# MotorDrive.net
KiCad netlist of a schematic drawn in Altium Designer
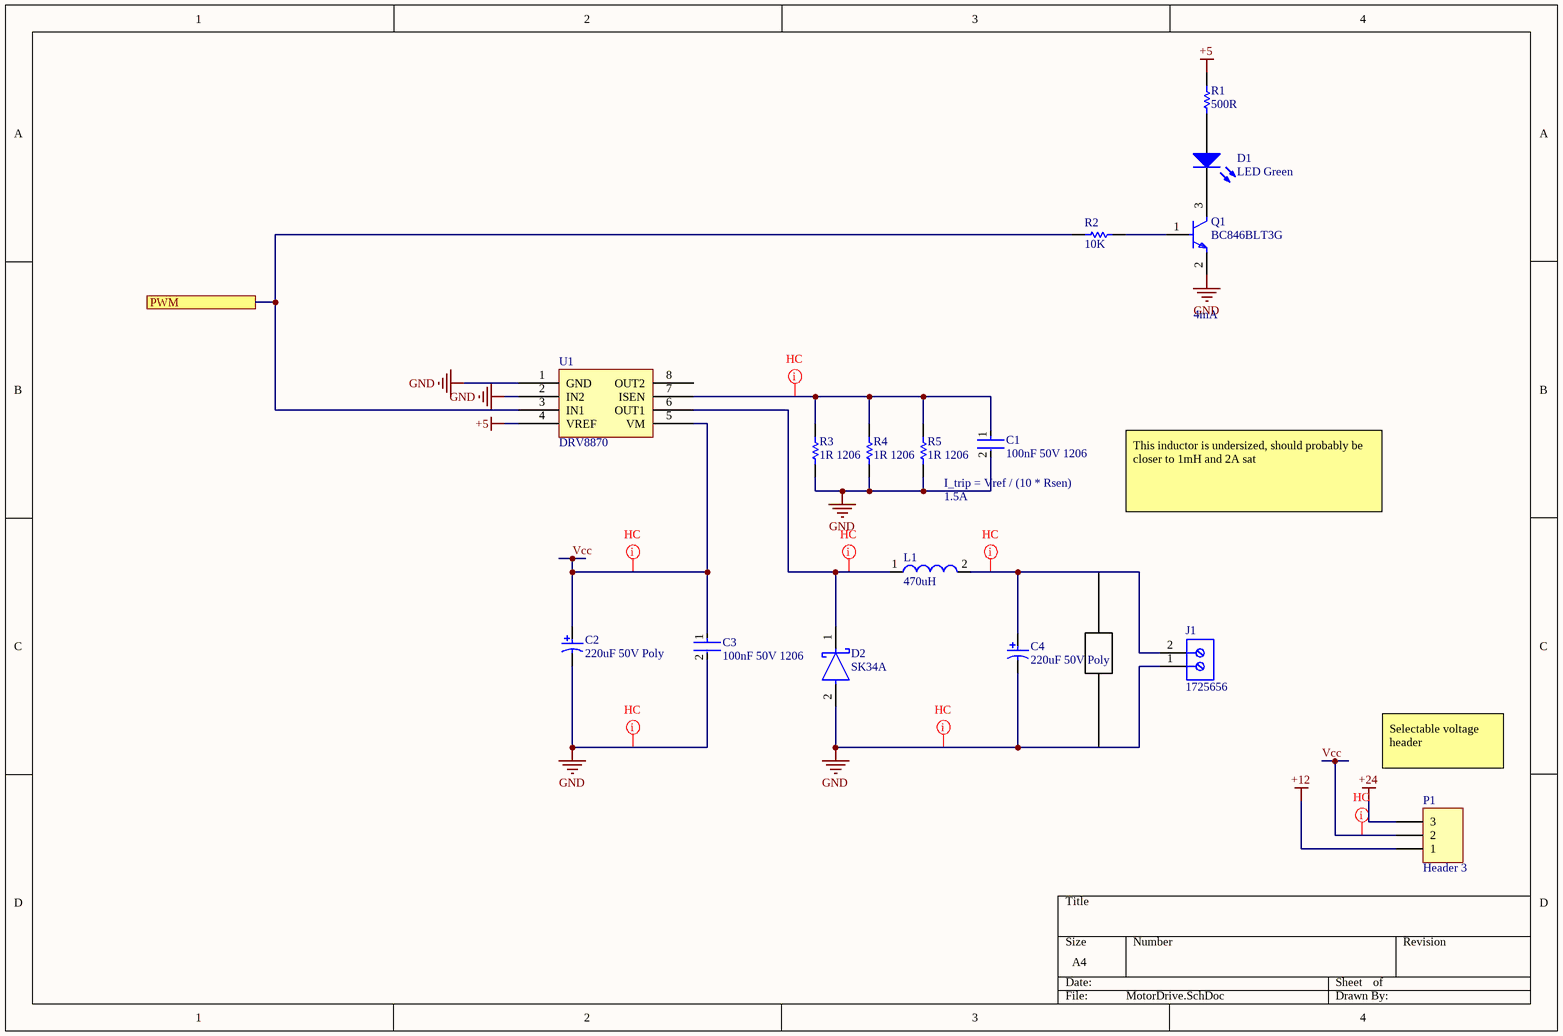
[diagram p0: MotorDrive.SchDoc]

(export (version "E")
  (design (tool "Eeschema 10.0.6"))
  (components
    (comp (ref "C1")
      (value "100nF 50V 1206")
      (footprint "FP-CL31-IPC_B")
      (description "Cap Ceramic 100nF 50V X7R ±10% SMD 1206 +125°C Embossed T/R")
      (fields (field (name "TOLERANCE") "10%"))
      (libsource (lib "Altium Content Vault") (part "b4654b650e69147ec39a6b967a45e02"))
    )
    (comp (ref "C2")
      (value "220uF 50V Poly")
      (footprint "CAPAE127P600-8N")
      (fields (field (name "VOLTAGE") "25VDC") (field (name "MANUFACTURER") "AVX"))
      (libsource (lib "Schlib1") (part "C-Poly"))
    )
    (comp (ref "C3")
      (value "100nF 50V 1206")
      (footprint "FP-CL31-IPC_B")
      (description "Cap Ceramic 100nF 50V X7R ±10% SMD 1206 +125°C Embossed T/R")
      (fields (field (name "TOLERANCE") "10%"))
      (libsource (lib "Altium Content Vault") (part "b4654b650e69147ec39a6b967a45e02"))
    )
    (comp (ref "C4")
      (value "220uF 50V Poly")
      (footprint "CAPAE127P600-8N")
      (fields (field (name "VOLTAGE") "25VDC") (field (name "MANUFACTURER") "AVX"))
      (libsource (lib "Schlib1") (part "C-Poly"))
    )
    (comp (ref "D1")
      (value "LED Green")
      (footprint "0603_A")
      (description "SMD mono-color Chip LED, WL-SMCW, Green")
      (fields (field (name "PARTNUMBER") "150060GS75000") (field (name "MANUFACTURER") "Wuerth Elektronik"))
      (libsource (lib "Altium Content Vault") (part "WE-LED_K1A2-2"))
    )
    (comp (ref "D2")
      (value "SK34A")
      (footprint "FP-DO-214AC-MFG")
      (description "DIODE SCHOTTKY 5A 30V SMA")
      (libsource (lib "Altium Content Vault") (part "1d6ec82d83fb6aee721767c19dac4b9"))
    )
    (comp (ref "J1")
      (value "1725656")
      (footprint "PHOE-1725656-2")
      (description "Male Header, Pitch 2.54 mm, 1 x 2 Position, Height 9 mm, Tail Length 3.5 mm")
      (fields (field (name "MANUFACTURER") "Phoenix Contact"))
      (libsource (lib "Altium Content Vault") (part "CN-1P-F-TB2"))
    )
    (comp (ref "L1")
      (value "470uH")
      (footprint "L1212")
      (fields (field (name "MANUFACTURER") "Wuerth Elektronik") (field (name "PARTNUMBER") "74479763215"))
      (libsource (lib "Schlib1") (part "Inductor1212"))
    )
    (comp (ref "P1")
      (value "Header 3")
      (footprint "HDR1X3")
      (description "Header, 3-Pin")
      (fields (field (name "PUBLISHER") "Altium Limited"))
      (libsource (lib "Miscellaneous Connectors") (part "Header 3"))
    )
    (comp (ref "Q1")
      (value "BC846BLT3G")
      (footprint "FP-318-08-IPC_C")
      (description "TRANS NPN 65V 0.1A SOT-23")
      (libsource (lib "Altium Content Vault") (part "2a1388f82443b098dcd57d24ac7632d"))
    )
    (comp (ref "R1")
      (value "500R")
      (footprint "RESC0603(1608)_L")
      (description "510R 0.1W 5% 0603 (1608 Metric)  SMD")
      (fields (field (name "POWER") "0.1 W") (field (name "TOLERANCE") "5 %"))
      (libsource (lib "Altium Content Vault") (part "RES"))
    )
    (comp (ref "R2")
      (value "10K")
      (footprint "RESC0603(1608)_N")
      (description "10K 0.1W 1% 0603 (1608 Metric)  SMD")
      (fields (field (name "POWER") "0.1 W") (field (name "TOLERANCE") "1 %"))
      (libsource (lib "Altium Content Vault") (part "RES"))
    )
    (comp (ref "R3")
      (value "1R 1206")
      (footprint "RESC1206(3216)_N")
      (description "1R2 0.25W 5% 1206 (3216 Metric)  SMD")
      (fields (field (name "POWER") "0.25 W") (field (name "TOLERANCE") "5 %"))
      (libsource (lib "Altium Content Vault") (part "RES"))
    )
    (comp (ref "R4")
      (value "1R 1206")
      (footprint "RESC1206(3216)_N")
      (description "1R2 0.25W 5% 1206 (3216 Metric)  SMD")
      (fields (field (name "POWER") "0.25 W") (field (name "TOLERANCE") "5 %"))
      (libsource (lib "Altium Content Vault") (part "RES"))
    )
    (comp (ref "R5")
      (value "1R 1206")
      (footprint "RESC1206(3216)_N")
      (description "1R2 0.25W 5% 1206 (3216 Metric)  SMD")
      (fields (field (name "POWER") "0.25 W") (field (name "TOLERANCE") "5 %"))
      (libsource (lib "Altium Content Vault") (part "RES"))
    )
    (comp (ref "U1")
      (value "DRV8870")
      (footprint "SOIC127P600X170_HS-9N")
      (libsource (lib "Schlib1") (part "DRV8870"))
    )
  )
  (nets
    (net (code "1") (name "+5") (class "Default")
      (node (ref "R1") (pin "2") (pinfunction "2_2") (pintype "passive"))
      (node (ref "U1") (pin "4") (pinfunction "VREF_4") (pintype "passive"))
    )
    (net (code "2") (name "+12") (class "Default")
      (node (ref "P1") (pin "1") (pinfunction "1_1") (pintype "passive"))
    )
    (net (code "3") (name "+24") (class "Default")
      (node (ref "P1") (pin "3") (pinfunction "3_3") (pintype "passive"))
    )
    (net (code "4") (name "/PWM") (class "Default")
      (node (ref "R2") (pin "1") (pinfunction "1_1") (pintype "passive"))
      (node (ref "U1") (pin "3") (pinfunction "IN1_3") (pintype "passive"))
    )
    (net (code "5") (name "/Vcc") (class "Default")
      (node (ref "C2") (pin "1") (pinfunction "1_1") (pintype "passive"))
      (node (ref "C3") (pin "1") (pinfunction "1_1") (pintype "passive"))
      (node (ref "P1") (pin "2") (pinfunction "2_2") (pintype "passive"))
      (node (ref "U1") (pin "5") (pinfunction "VM_5") (pintype "passive"))
    )
    (net (code "6") (name "GND") (class "Default")
      (node (ref "C1") (pin "2") (pinfunction "2_2") (pintype "passive"))
      (node (ref "C2") (pin "2") (pinfunction "2_2") (pintype "passive"))
      (node (ref "C3") (pin "2") (pinfunction "2_2") (pintype "passive"))
      (node (ref "C4") (pin "2") (pinfunction "2_2") (pintype "passive"))
      (node (ref "D2") (pin "2") (pinfunction "A_2") (pintype "passive"))
      (node (ref "J1") (pin "1") (pinfunction "1_1") (pintype "passive"))
      (node (ref "Q1") (pin "2") (pinfunction "E_2") (pintype "passive"))
      (node (ref "R3") (pin "1") (pinfunction "1_1") (pintype "passive"))
      (node (ref "R4") (pin "1") (pinfunction "1_1") (pintype "passive"))
      (node (ref "R5") (pin "1") (pinfunction "1_1") (pintype "passive"))
      (node (ref "U1") (pin "1") (pinfunction "GND_1") (pintype "passive"))
      (node (ref "U1") (pin "2") (pinfunction "IN2_2") (pintype "passive"))
    )
    (net (code "7") (name "Net-(C4-Pad1)") (class "Default")
      (node (ref "C4") (pin "1") (pinfunction "1_1") (pintype "passive"))
      (node (ref "J1") (pin "2") (pinfunction "2_2") (pintype "passive"))
      (node (ref "L1") (pin "2") (pinfunction "2_2") (pintype "passive"))
    )
    (net (code "8") (name "Net-(D1-A)") (class "Default")
      (node (ref "D1") (pin "2") (pinfunction "A_2") (pintype "passive"))
      (node (ref "R1") (pin "1") (pinfunction "1_1") (pintype "passive"))
    )
    (net (code "9") (name "Net-(D1-K)") (class "Default")
      (node (ref "D1") (pin "1") (pinfunction "K_1") (pintype "passive"))
      (node (ref "Q1") (pin "3") (pinfunction "C_3") (pintype "passive"))
    )
    (net (code "10") (name "Net-(D2-C)") (class "Default")
      (node (ref "D2") (pin "1") (pinfunction "C_1") (pintype "passive"))
      (node (ref "L1") (pin "1") (pinfunction "1_1") (pintype "passive"))
      (node (ref "U1") (pin "6") (pinfunction "OUT1_6") (pintype "passive"))
    )
    (net (code "11") (name "Net-(Q1-B)") (class "Default")
      (node (ref "Q1") (pin "1") (pinfunction "B_1") (pintype "passive"))
      (node (ref "R2") (pin "2") (pinfunction "2_2") (pintype "passive"))
    )
    (net (code "12") (name "Net-(U1-ISEN)") (class "Default")
      (node (ref "C1") (pin "1") (pinfunction "1_1") (pintype "passive"))
      (node (ref "R3") (pin "2") (pinfunction "2_2") (pintype "passive"))
      (node (ref "R4") (pin "2") (pinfunction "2_2") (pintype "passive"))
      (node (ref "R5") (pin "2") (pinfunction "2_2") (pintype "passive"))
      (node (ref "U1") (pin "7") (pinfunction "ISEN_7") (pintype "passive"))
    )
    (net (code "13") (name "unconnected-(U1-OUT2-Pad8)") (class "Default")
      (node (ref "U1") (pin "8") (pinfunction "OUT2_8") (pintype "passive"))
    )
  )
)
